# core_mcu.net
KiCad netlist of a schematic drawn in EAGLE
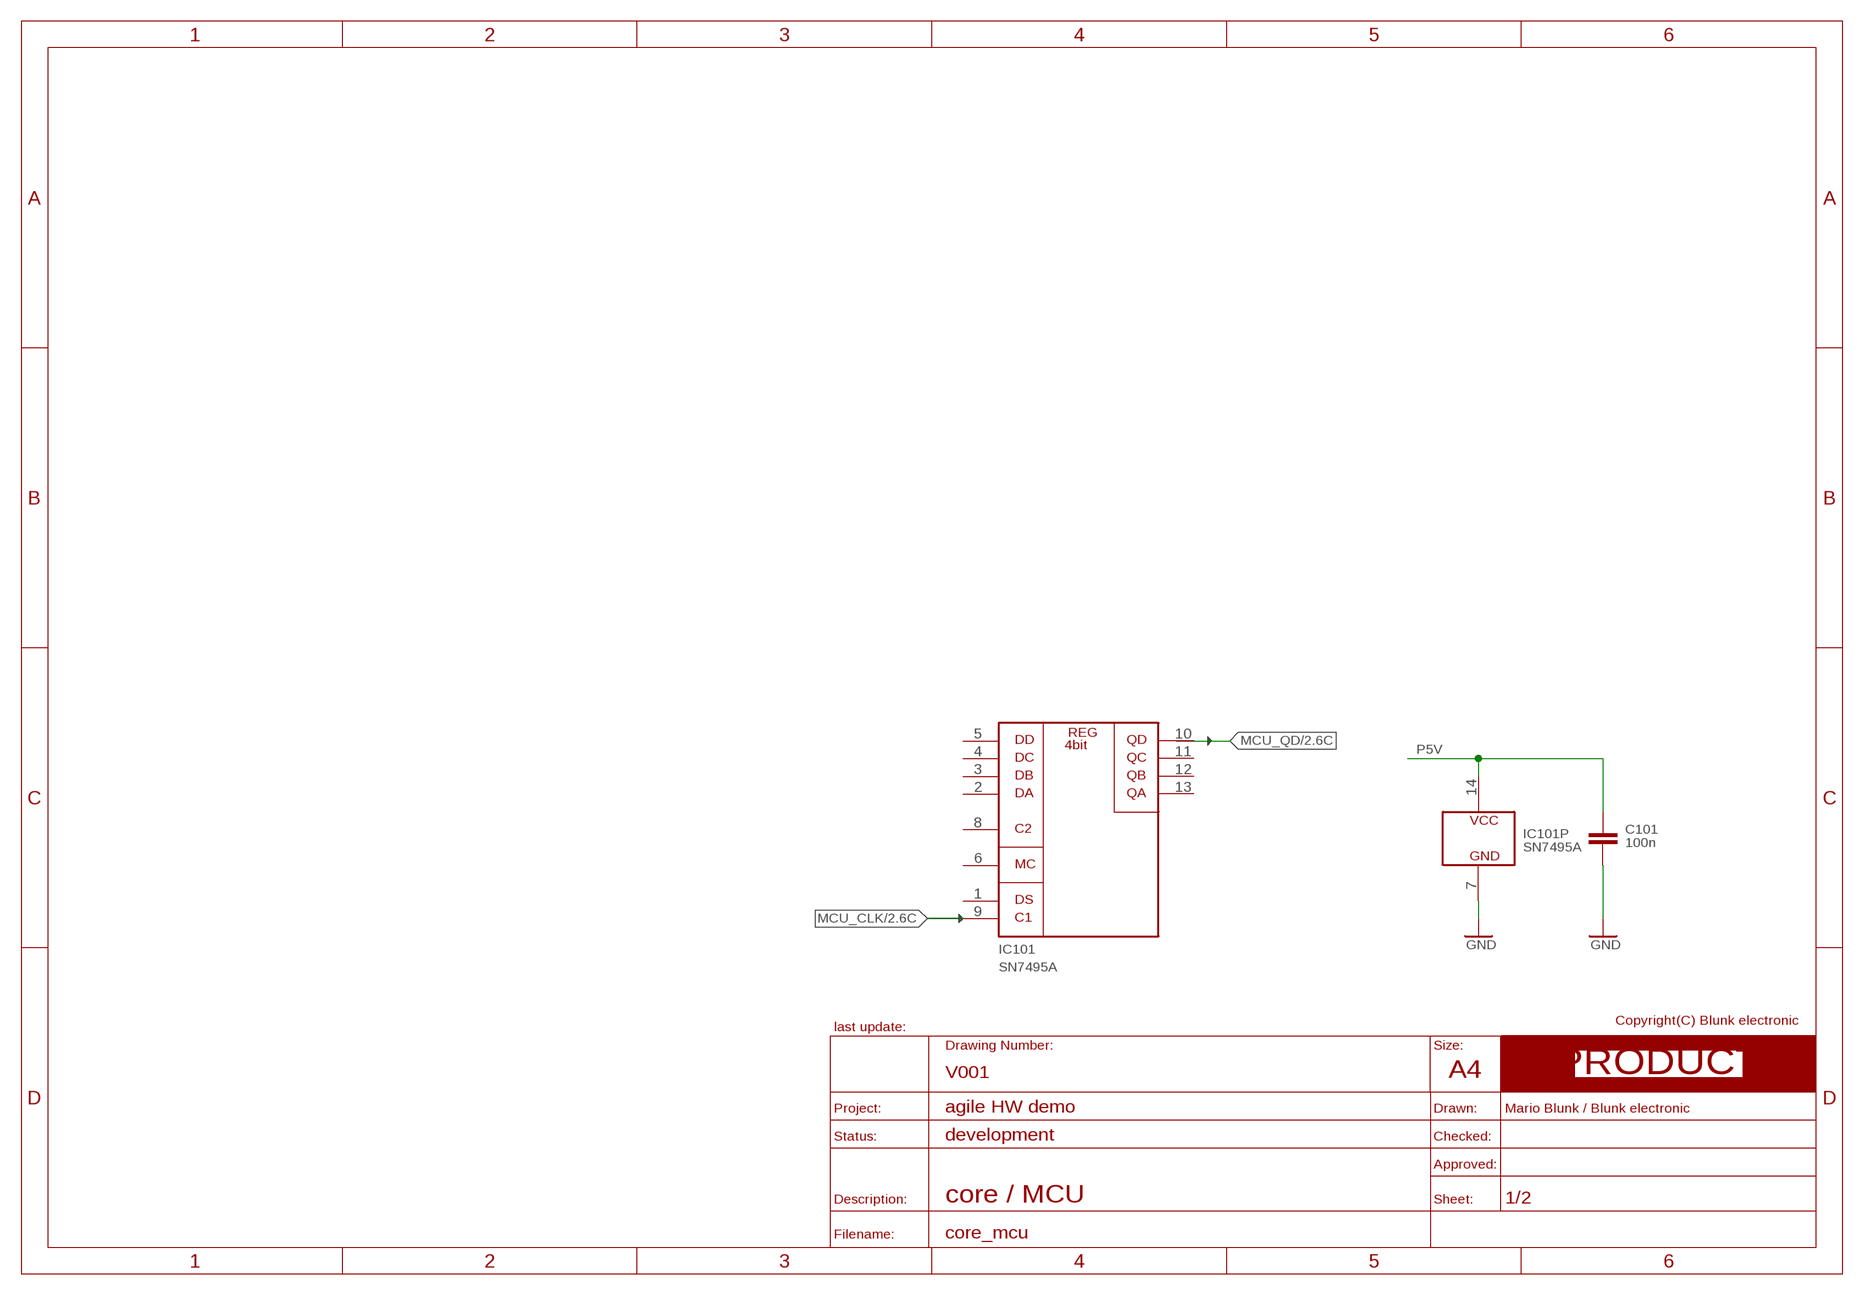
[diagram p0: schematic, sheet 1]
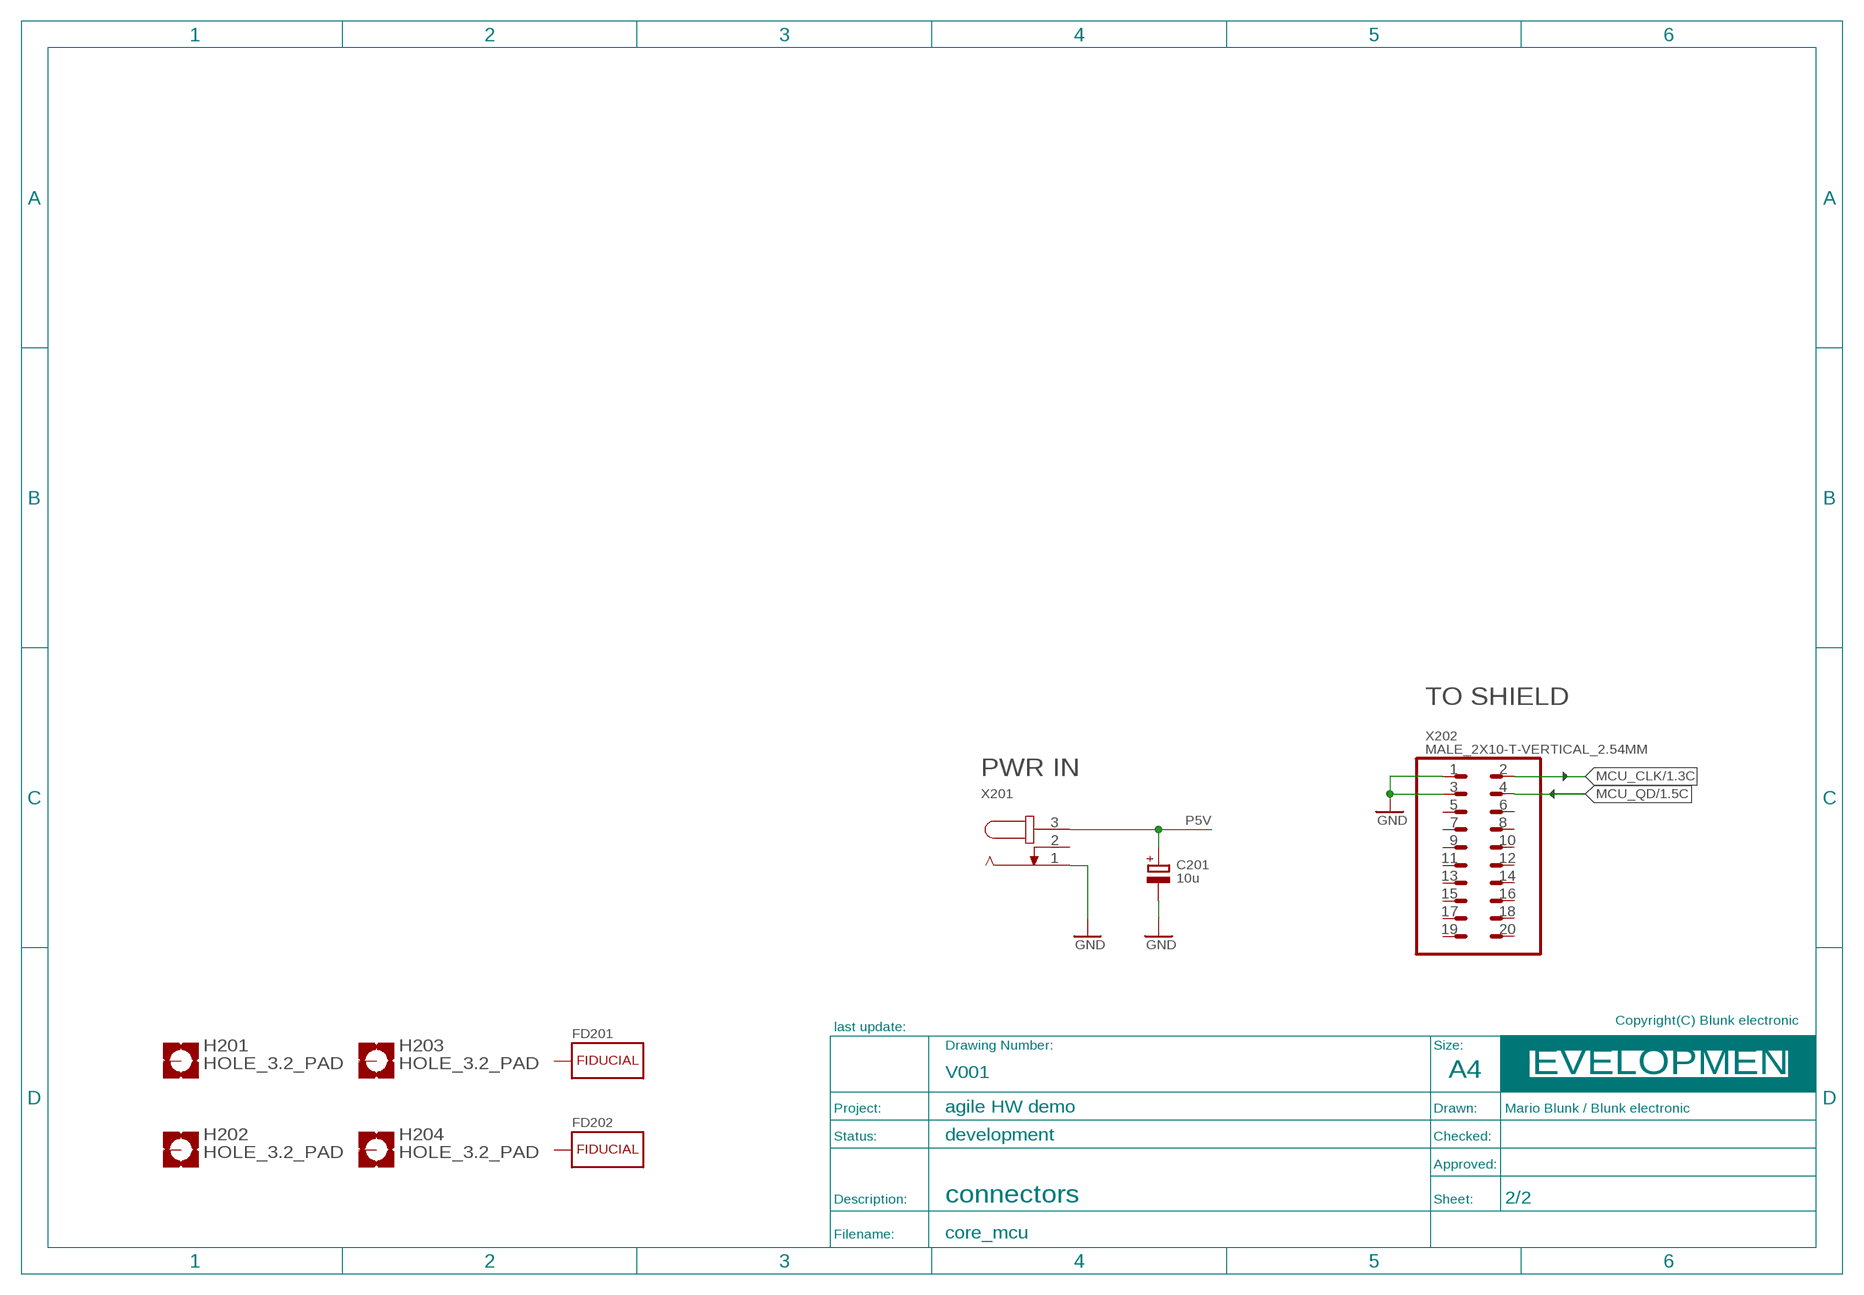
[diagram p1: schematic, sheet 2]

(export (version "E")
  (design (tool "Eeschema 10.0.6"))
  (components
    (comp (ref "C101")
      (value "100n")
      (footprint "eagle-import:S_0805")
      (fields (field (name "PART_CODE_BEL") "C_PAC_S_0805_VAL_100n"))
      (libsource (lib "eagle-import") (part "C_S_0805"))
    )
    (comp (ref "IC101")
      (value "SN7495A")
      (footprint "eagle-import:T_NDIP14")
      (libsource (lib "eagle-import") (part "7495A"))
    )
    (comp (ref "C201")
      (value "10u")
      (footprint "eagle-import:S_6032")
      (fields (field (name "PART_CODE_BEL") "C_PAC_S_6032_VAL_10u_Vmax_35V"))
      (libsource (lib "eagle-import") (part "C_POL_S_6032"))
    )
    (comp (ref "FD201")
      (value "FIDUCIAL_CROSSHAIR")
      (footprint "eagle-import:CROSSHAIR")
      (libsource (lib "eagle-import") (part "FIDUCIAL_CROSSHAIR"))
    )
    (comp (ref "FD202")
      (value "FIDUCIAL_CROSSHAIR")
      (footprint "eagle-import:CROSSHAIR")
      (libsource (lib "eagle-import") (part "FIDUCIAL_CROSSHAIR"))
    )
    (comp (ref "H201")
      (value "HOLE_3.2_PAD")
      (footprint "eagle-import:3.2_PAD")
      (libsource (lib "eagle-import") (part "HOLE_3.2_PAD"))
    )
    (comp (ref "H202")
      (value "HOLE_3.2_PAD")
      (footprint "eagle-import:3.2_PAD")
      (libsource (lib "eagle-import") (part "HOLE_3.2_PAD"))
    )
    (comp (ref "H203")
      (value "HOLE_3.2_PAD")
      (footprint "eagle-import:3.2_PAD")
      (libsource (lib "eagle-import") (part "HOLE_3.2_PAD"))
    )
    (comp (ref "H204")
      (value "HOLE_3.2_PAD")
      (footprint "eagle-import:3.2_PAD")
      (libsource (lib "eagle-import") (part "HOLE_3.2_PAD"))
    )
    (comp (ref "X201")
      (value "POWER_JACK-T-0")
      (footprint "eagle-import:T_POWER_JACK_SPC4077")
      (fields (field (name "FUNCTION") "PWR IN"))
      (libsource (lib "eagle-import") (part "POWER_JACK-T-0"))
    )
    (comp (ref "X202")
      (value "MALE_2X10-T-VERTICAL_2.54MM")
      (footprint "eagle-import:T_MALE_2X10_VERTICAL_GRID_2.54MM")
      (fields
        (field (name "FUNCTION") "TO SHIELD")
        (field (name "PART_CODE_BEL") "X_PAC_T_MALE_2X10_VERTICAL_PITCH_2mm54")
      )
      (libsource (lib "eagle-import") (part "MALE_2X10-T-VERTICAL_2.54MM"))
    )
  )
  (nets
    (net (code "1") (name "GND") (class "Default")
      (node (ref "C101") (pin "2") (pinfunction "2_2") (pintype "passive"))
      (node (ref "C201") (pin "-") (pinfunction "-_-") (pintype "passive"))
      (node (ref "IC101") (pin "7") (pinfunction "GND_7") (pintype "power_in"))
      (node (ref "X201") (pin "1") (pinfunction "1_1") (pintype "passive"))
      (node (ref "X202") (pin "1") (pinfunction "1_1") (pintype "passive"))
      (node (ref "X202") (pin "3") (pinfunction "3_3") (pintype "passive"))
    )
    (net (code "2") (name "MCU_CLK") (class "Default")
      (node (ref "IC101") (pin "9") (pinfunction "C1_9") (pintype "input"))
      (node (ref "X202") (pin "2") (pinfunction "2_2") (pintype "passive"))
    )
    (net (code "3") (name "MCU_QD") (class "Default")
      (node (ref "IC101") (pin "10") (pinfunction "QD_10") (pintype "output"))
      (node (ref "X202") (pin "4") (pinfunction "4_4") (pintype "passive"))
    )
    (net (code "4") (name "P5V") (class "Default")
      (node (ref "C101") (pin "1") (pinfunction "1_1") (pintype "passive"))
      (node (ref "C201") (pin "+") (pinfunction "+_+") (pintype "passive"))
      (node (ref "IC101") (pin "14") (pinfunction "VCC_14") (pintype "power_in"))
      (node (ref "X201") (pin "3") (pinfunction "3_3") (pintype "passive"))
    )
    (net (code "5") (name "unconnected-(FD201-NC-Pad1)") (class "Default")
      (node (ref "FD201") (pin "1") (pinfunction "NC_1") (pintype "no_connect"))
    )
    (net (code "6") (name "unconnected-(FD202-NC-Pad1)") (class "Default")
      (node (ref "FD202") (pin "1") (pinfunction "NC_1") (pintype "no_connect"))
    )
    (net (code "7") (name "unconnected-(H201-MOUNT-PadH1)") (class "Default")
      (node (ref "H201") (pin "H1") (pinfunction "MOUNT_H1") (pintype "passive"))
    )
    (net (code "8") (name "unconnected-(H202-MOUNT-PadH1)") (class "Default")
      (node (ref "H202") (pin "H1") (pinfunction "MOUNT_H1") (pintype "passive"))
    )
    (net (code "9") (name "unconnected-(H203-MOUNT-PadH1)") (class "Default")
      (node (ref "H203") (pin "H1") (pinfunction "MOUNT_H1") (pintype "passive"))
    )
    (net (code "10") (name "unconnected-(H204-MOUNT-PadH1)") (class "Default")
      (node (ref "H204") (pin "H1") (pinfunction "MOUNT_H1") (pintype "passive"))
    )
    (net (code "11") (name "unconnected-(IC101A-C2-Pad8)") (class "Default")
      (node (ref "IC101") (pin "8") (pinfunction "C2_8") (pintype "input"))
    )
    (net (code "12") (name "unconnected-(IC101A-DA-Pad2)") (class "Default")
      (node (ref "IC101") (pin "2") (pinfunction "DA_2") (pintype "input"))
    )
    (net (code "13") (name "unconnected-(IC101A-DB-Pad3)") (class "Default")
      (node (ref "IC101") (pin "3") (pinfunction "DB_3") (pintype "input"))
    )
    (net (code "14") (name "unconnected-(IC101A-DC-Pad4)") (class "Default")
      (node (ref "IC101") (pin "4") (pinfunction "DC_4") (pintype "input"))
    )
    (net (code "15") (name "unconnected-(IC101A-DD-Pad5)") (class "Default")
      (node (ref "IC101") (pin "5") (pinfunction "DD_5") (pintype "input"))
    )
    (net (code "16") (name "unconnected-(IC101A-DS-Pad1)") (class "Default")
      (node (ref "IC101") (pin "1") (pinfunction "DS_1") (pintype "input"))
    )
    (net (code "17") (name "unconnected-(IC101A-MC-Pad6)") (class "Default")
      (node (ref "IC101") (pin "6") (pinfunction "MC_6") (pintype "input"))
    )
    (net (code "18") (name "unconnected-(IC101A-QA-Pad13)") (class "Default")
      (node (ref "IC101") (pin "13") (pinfunction "QA_13") (pintype "output"))
    )
    (net (code "19") (name "unconnected-(IC101A-QB-Pad12)") (class "Default")
      (node (ref "IC101") (pin "12") (pinfunction "QB_12") (pintype "output"))
    )
    (net (code "20") (name "unconnected-(IC101A-QC-Pad11)") (class "Default")
      (node (ref "IC101") (pin "11") (pinfunction "QC_11") (pintype "output"))
    )
    (net (code "21") (name "unconnected-(X201-Pad2)") (class "Default")
      (node (ref "X201") (pin "2") (pinfunction "2_2") (pintype "passive"))
    )
    (net (code "22") (name "unconnected-(X202-Pad5)") (class "Default")
      (node (ref "X202") (pin "5") (pinfunction "5_5") (pintype "passive"))
    )
    (net (code "23") (name "unconnected-(X202-Pad6)") (class "Default")
      (node (ref "X202") (pin "6") (pinfunction "6_6") (pintype "passive"))
    )
    (net (code "24") (name "unconnected-(X202-Pad7)") (class "Default")
      (node (ref "X202") (pin "7") (pinfunction "7_7") (pintype "passive"))
    )
    (net (code "25") (name "unconnected-(X202-Pad8)") (class "Default")
      (node (ref "X202") (pin "8") (pinfunction "8_8") (pintype "passive"))
    )
    (net (code "26") (name "unconnected-(X202-Pad9)") (class "Default")
      (node (ref "X202") (pin "9") (pinfunction "9_9") (pintype "passive"))
    )
    (net (code "27") (name "unconnected-(X202-Pad10)") (class "Default")
      (node (ref "X202") (pin "10") (pinfunction "10_10") (pintype "passive"))
    )
    (net (code "28") (name "unconnected-(X202-Pad11)") (class "Default")
      (node (ref "X202") (pin "11") (pinfunction "11_11") (pintype "passive"))
    )
    (net (code "29") (name "unconnected-(X202-Pad12)") (class "Default")
      (node (ref "X202") (pin "12") (pinfunction "12_12") (pintype "passive"))
    )
    (net (code "30") (name "unconnected-(X202-Pad13)") (class "Default")
      (node (ref "X202") (pin "13") (pinfunction "13_13") (pintype "passive"))
    )
    (net (code "31") (name "unconnected-(X202-Pad14)") (class "Default")
      (node (ref "X202") (pin "14") (pinfunction "14_14") (pintype "passive"))
    )
    (net (code "32") (name "unconnected-(X202-Pad15)") (class "Default")
      (node (ref "X202") (pin "15") (pinfunction "15_15") (pintype "passive"))
    )
    (net (code "33") (name "unconnected-(X202-Pad16)") (class "Default")
      (node (ref "X202") (pin "16") (pinfunction "16_16") (pintype "passive"))
    )
    (net (code "34") (name "unconnected-(X202-Pad17)") (class "Default")
      (node (ref "X202") (pin "17") (pinfunction "17_17") (pintype "passive"))
    )
    (net (code "35") (name "unconnected-(X202-Pad18)") (class "Default")
      (node (ref "X202") (pin "18") (pinfunction "18_18") (pintype "passive"))
    )
    (net (code "36") (name "unconnected-(X202-Pad19)") (class "Default")
      (node (ref "X202") (pin "19") (pinfunction "19_19") (pintype "passive"))
    )
    (net (code "37") (name "unconnected-(X202-Pad20)") (class "Default")
      (node (ref "X202") (pin "20") (pinfunction "20_20") (pintype "passive"))
    )
  )
)
